# CompSchm.net
KiCad netlist of a schematic drawn in Altium Designer
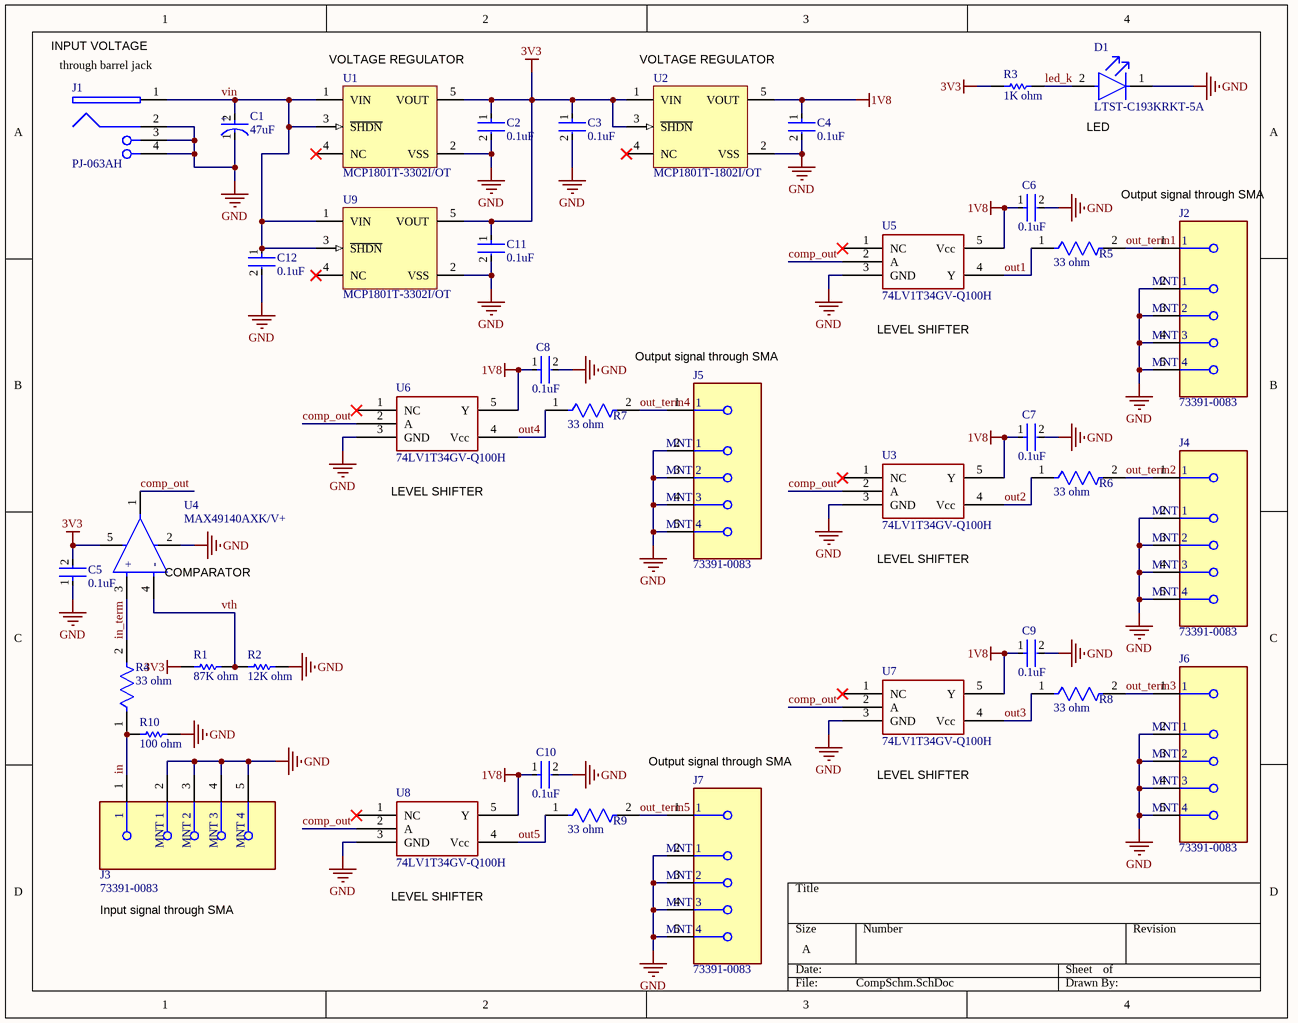
[diagram p0: CompSchm.SchDoc]

(export (version "E")
  (design (tool "Eeschema 10.0.6"))
  (components
    (comp (ref "C1")
      (value "47uF")
      (footprint "FP-T491X476K035AT-MFG")
      (description "CAP TANT 47UF 10% 35V 2917 Part: T491X476K035AT")
      (fields (field (name "TOLERANCE") "10%") (field (name "VOLTAGE") "35V"))
      (libsource (lib "Altium Content Vault") (part "203bc49f2ac43e59fd269a8c329ed05"))
    )
    (comp (ref "C2")
      (value "0.1uF")
      (footprint "FP-CL21-IPC_C")
      (description "CL21 Series 0805 100nF 25V ±10% Tolerance X7R Multilayer Ceramic Chip Capacitor")
      (fields (field (name "VOLTAGE") "25V") (field (name "TOLERANCE") "10%"))
      (libsource (lib "Altium Content Vault") (part "b4654b650e69147ec39a6b967a45e02"))
    )
    (comp (ref "C3")
      (value "0.1uF")
      (footprint "FP-CL21-IPC_C")
      (description "CL21 Series 0805 100nF 25V ±10% Tolerance X7R Multilayer Ceramic Chip Capacitor")
      (fields (field (name "VOLTAGE") "25V") (field (name "TOLERANCE") "10%"))
      (libsource (lib "Altium Content Vault") (part "b4654b650e69147ec39a6b967a45e02"))
    )
    (comp (ref "C4")
      (value "0.1uF")
      (footprint "FP-CL21-IPC_C")
      (description "CL21 Series 0805 100nF 25V ±10% Tolerance X7R Multilayer Ceramic Chip Capacitor")
      (fields (field (name "VOLTAGE") "25V") (field (name "TOLERANCE") "10%"))
      (libsource (lib "Altium Content Vault") (part "b4654b650e69147ec39a6b967a45e02"))
    )
    (comp (ref "C5")
      (value "0.1uF")
      (footprint "FP-CL21-IPC_C")
      (description "CL21 Series 0805 100nF 25V ±10% Tolerance X7R Multilayer Ceramic Chip Capacitor")
      (fields (field (name "VOLTAGE") "25V") (field (name "TOLERANCE") "10%"))
      (libsource (lib "Altium Content Vault") (part "b4654b650e69147ec39a6b967a45e02"))
    )
    (comp (ref "C6")
      (value "0.1uF")
      (footprint "FP-CL21-IPC_C")
      (description "CL21 Series 0805 100nF 25V ±10% Tolerance X7R Multilayer Ceramic Chip Capacitor")
      (fields (field (name "VOLTAGE") "25V") (field (name "TOLERANCE") "10%"))
      (libsource (lib "Altium Content Vault") (part "b4654b650e69147ec39a6b967a45e02"))
    )
    (comp (ref "C7")
      (value "0.1uF")
      (footprint "FP-CL21-IPC_C")
      (description "CL21 Series 0805 100nF 25V ±10% Tolerance X7R Multilayer Ceramic Chip Capacitor")
      (fields (field (name "VOLTAGE") "25V") (field (name "TOLERANCE") "10%"))
      (libsource (lib "Altium Content Vault") (part "b4654b650e69147ec39a6b967a45e02"))
    )
    (comp (ref "C8")
      (value "0.1uF")
      (footprint "FP-CL21-IPC_C")
      (description "CL21 Series 0805 100nF 25V ±10% Tolerance X7R Multilayer Ceramic Chip Capacitor")
      (fields (field (name "VOLTAGE") "25V") (field (name "TOLERANCE") "10%"))
      (libsource (lib "Altium Content Vault") (part "b4654b650e69147ec39a6b967a45e02"))
    )
    (comp (ref "C9")
      (value "0.1uF")
      (footprint "FP-CL21-IPC_C")
      (description "CL21 Series 0805 100nF 25V ±10% Tolerance X7R Multilayer Ceramic Chip Capacitor")
      (fields (field (name "VOLTAGE") "25V") (field (name "TOLERANCE") "10%"))
      (libsource (lib "Altium Content Vault") (part "b4654b650e69147ec39a6b967a45e02"))
    )
    (comp (ref "C10")
      (value "0.1uF")
      (footprint "FP-CL21-IPC_C")
      (description "CL21 Series 0805 100nF 25V ±10% Tolerance X7R Multilayer Ceramic Chip Capacitor")
      (fields (field (name "VOLTAGE") "25V") (field (name "TOLERANCE") "10%"))
      (libsource (lib "Altium Content Vault") (part "b4654b650e69147ec39a6b967a45e02"))
    )
    (comp (ref "C11")
      (value "0.1uF")
      (footprint "FP-CL21-IPC_C")
      (description "CL21 Series 0805 100nF 25V ±10% Tolerance X7R Multilayer Ceramic Chip Capacitor")
      (fields (field (name "VOLTAGE") "25V") (field (name "TOLERANCE") "10%"))
      (libsource (lib "Altium Content Vault") (part "b4654b650e69147ec39a6b967a45e02"))
    )
    (comp (ref "C12")
      (value "0.1uF")
      (footprint "FP-CL21-IPC_C")
      (description "CL21 Series 0805 100nF 25V ±10% Tolerance X7R Multilayer Ceramic Chip Capacitor")
      (fields (field (name "VOLTAGE") "25V") (field (name "TOLERANCE") "10%"))
      (libsource (lib "Altium Content Vault") (part "b4654b650e69147ec39a6b967a45e02"))
    )
    (comp (ref "D1")
      (value "LTST-C193KRKT-5A")
      (footprint "FP-LTST-C193KRKT-5A-MFG")
      (description "LED RED CLEAR CHIP SMD")
      (libsource (lib "Altium Content Vault") (part "8706943c75ba83719d021d2fdc84c58"))
    )
    (comp (ref "J1")
      (value "PJ-063AH")
      (footprint "CUI-PJ-063AH_V")
      (fields (field (name "MANUFACTURER") "CUIInc."))
      (libsource (lib "Altium Content Vault") (part "JACK-2CD2_A"))
    )
    (comp (ref "J2")
      (value "73391-0083")
      (footprint "FP-73391-0083-MFG")
      (description "SMA RA JACK, PCB")
      (libsource (lib "Altium Content Vault") (part "c65b8a639cdaef1819ea20b5466f8fa"))
    )
    (comp (ref "J3")
      (value "73391-0083")
      (footprint "FP-73391-0083-MFG")
      (description "SMA RA JACK, PCB")
      (libsource (lib "") (part "c65b8a639cdaef1819ea20b5466f8fa_1"))
    )
    (comp (ref "J4")
      (value "73391-0083")
      (footprint "FP-73391-0083-MFG")
      (description "SMA RA JACK, PCB")
      (libsource (lib "Altium Content Vault") (part "c65b8a639cdaef1819ea20b5466f8fa"))
    )
    (comp (ref "J5")
      (value "73391-0083")
      (footprint "FP-73391-0083-MFG")
      (description "SMA RA JACK, PCB")
      (libsource (lib "Altium Content Vault") (part "c65b8a639cdaef1819ea20b5466f8fa"))
    )
    (comp (ref "J6")
      (value "73391-0083")
      (footprint "FP-73391-0083-MFG")
      (description "SMA RA JACK, PCB")
      (libsource (lib "Altium Content Vault") (part "c65b8a639cdaef1819ea20b5466f8fa"))
    )
    (comp (ref "J7")
      (value "73391-0083")
      (footprint "FP-73391-0083-MFG")
      (description "SMA RA JACK, PCB")
      (libsource (lib "Altium Content Vault") (part "c65b8a639cdaef1819ea20b5466f8fa"))
    )
    (comp (ref "R1")
      (value "87K ohm")
      (footprint "RESC2013X50X40NL20T20")
      (fields (field (name "PART NUMBER") "RG2012N-123-W-T1") (field (name "MANUFACTURER") "Susumu"))
      (libsource (lib "Altium Content Vault") (part "RES"))
    )
    (comp (ref "R2")
      (value "12K ohm")
      (footprint "RESC2013X50X40NL20T20")
      (fields (field (name "PART NUMBER") "RG2012N-123-W-T1") (field (name "MANUFACTURER") "Susumu"))
      (libsource (lib "Altium Content Vault") (part "RES"))
    )
    (comp (ref "R3")
      (value "1K ohm")
      (footprint "RESC2013X50X40NL20T20")
      (fields (field (name "PART NUMBER") "RG2012N-123-W-T1") (field (name "MANUFACTURER") "Susumu"))
      (libsource (lib "Altium Content Vault") (part "RES"))
    )
    (comp (ref "R4")
      (value "33 ohm")
      (footprint "FP-CRGCQ0805-IPC_C")
      (description "CRGCQ0805 33Ω 0.125W ±200ppm/°C 1% 150V")
      (fields
        (field (name "MANUFACTURER PART NUMBER") "CRGCQ0805F33R")
        (field (name "MANUFACTURER") "TE Connectivity")
      )
      (libsource (lib "Altium Content Vault") (part "1029c3af85768c4190bb7ad29bc67b5"))
    )
    (comp (ref "R5")
      (value "33 ohm")
      (footprint "FP-CRGCQ0805-IPC_C")
      (description "CRGCQ0805 33Ω 0.125W ±200ppm/°C 1% 150V")
      (fields
        (field (name "MANUFACTURER PART NUMBER") "CRGCQ0805F33R")
        (field (name "MANUFACTURER") "TE Connectivity")
      )
      (libsource (lib "Altium Content Vault") (part "1029c3af85768c4190bb7ad29bc67b5"))
    )
    (comp (ref "R6")
      (value "33 ohm")
      (footprint "FP-CRGCQ0805-IPC_C")
      (description "CRGCQ0805 33Ω 0.125W ±200ppm/°C 1% 150V")
      (fields
        (field (name "MANUFACTURER PART NUMBER") "CRGCQ0805F33R")
        (field (name "MANUFACTURER") "TE Connectivity")
      )
      (libsource (lib "Altium Content Vault") (part "1029c3af85768c4190bb7ad29bc67b5"))
    )
    (comp (ref "R7")
      (value "33 ohm")
      (footprint "FP-CRGCQ0805-IPC_C")
      (description "CRGCQ0805 33Ω 0.125W ±200ppm/°C 1% 150V")
      (fields
        (field (name "MANUFACTURER PART NUMBER") "CRGCQ0805F33R")
        (field (name "MANUFACTURER") "TE Connectivity")
      )
      (libsource (lib "Altium Content Vault") (part "1029c3af85768c4190bb7ad29bc67b5"))
    )
    (comp (ref "R8")
      (value "33 ohm")
      (footprint "FP-CRGCQ0805-IPC_C")
      (description "CRGCQ0805 33Ω 0.125W ±200ppm/°C 1% 150V")
      (fields
        (field (name "MANUFACTURER PART NUMBER") "CRGCQ0805F33R")
        (field (name "MANUFACTURER") "TE Connectivity")
      )
      (libsource (lib "Altium Content Vault") (part "1029c3af85768c4190bb7ad29bc67b5"))
    )
    (comp (ref "R9")
      (value "33 ohm")
      (footprint "FP-CRGCQ0805-IPC_C")
      (description "CRGCQ0805 33Ω 0.125W ±200ppm/°C 1% 150V")
      (fields
        (field (name "MANUFACTURER PART NUMBER") "CRGCQ0805F33R")
        (field (name "MANUFACTURER") "TE Connectivity")
      )
      (libsource (lib "Altium Content Vault") (part "1029c3af85768c4190bb7ad29bc67b5"))
    )
    (comp (ref "R10")
      (value "100 ohm")
      (footprint "RESC2013X50X40NL20T20")
      (fields (field (name "PART NUMBER") "RG2012N-123-W-T1") (field (name "MANUFACTURER") "Susumu"))
      (libsource (lib "Altium Content Vault") (part "RES"))
    )
    (comp (ref "U1")
      (value "MCP1801T-3302I/OT")
      (footprint "SOT-23-OT5_M")
      (description "150 mA, High PSRR, Low Quiescent Current LDO, 5-Pin SOT-23, Industrial Temperature, Tape and Reel")
      (libsource (lib "Altium Content Vault") (part "PM-LINEREG-MCP1801-IL5"))
    )
    (comp (ref "U2")
      (value "MCP1801T-1802I/OT")
      (footprint "SOT-23-OT5_M")
      (description "150 mA, High PSRR, Low Quiescent Current LDO, 5-Pin SOT-23, Industrial Temperature, Tape and Reel")
      (libsource (lib "Altium Content Vault") (part "PM-LINEREG-MCP1801-IL5"))
    )
    (comp (ref "U3")
      (value "74LV1T34GV-Q100H")
      (footprint "SOT95P275X110-5N:SOT95P275X110-5N")
      (description "Level Shifter")
      (libsource (lib "74LV1T34GV-Q100H") (part "74LV1T34GV-Q100H"))
    )
    (comp (ref "U4")
      (value "MAX49140AXK/V+")
      (footprint "FP-X5-1C-MFG")
      (description "30NS, LOW-POWER, 3V/5V, RAIL-TO-")
      (libsource (lib "Altium Content Vault") (part "3063e83f23e6bb72aa5a98f7fedc5b1"))
    )
    (comp (ref "U5")
      (value "74LV1T34GV-Q100H")
      (footprint "SOT95P275X110-5N:SOT95P275X110-5N")
      (description "Level Shifter")
      (libsource (lib "74LV1T34GV-Q100H") (part "74LV1T34GV-Q100H"))
    )
    (comp (ref "U6")
      (value "74LV1T34GV-Q100H")
      (footprint "SOT95P275X110-5N:SOT95P275X110-5N")
      (description "Level Shifter")
      (libsource (lib "74LV1T34GV-Q100H") (part "74LV1T34GV-Q100H"))
    )
    (comp (ref "U7")
      (value "74LV1T34GV-Q100H")
      (footprint "SOT95P275X110-5N:SOT95P275X110-5N")
      (description "Level Shifter")
      (libsource (lib "74LV1T34GV-Q100H") (part "74LV1T34GV-Q100H"))
    )
    (comp (ref "U8")
      (value "74LV1T34GV-Q100H")
      (footprint "SOT95P275X110-5N:SOT95P275X110-5N")
      (description "Level Shifter")
      (libsource (lib "74LV1T34GV-Q100H") (part "74LV1T34GV-Q100H"))
    )
    (comp (ref "U9")
      (value "MCP1801T-3302I/OT")
      (footprint "SOT-23-OT5_M")
      (description "150 mA, High PSRR, Low Quiescent Current LDO, 5-Pin SOT-23, Industrial Temperature, Tape and Reel")
      (libsource (lib "Altium Content Vault") (part "PM-LINEREG-MCP1801-IL5"))
    )
  )
  (nets
    (net (code "1") (name "/comp_out") (class "Default")
      (node (ref "U3") (pin "2") (pinfunction "A_2") (pintype "passive"))
      (node (ref "U4") (pin "1") (pinfunction "OUT_1") (pintype "passive"))
      (node (ref "U5") (pin "2") (pinfunction "A_2") (pintype "passive"))
      (node (ref "U6") (pin "2") (pinfunction "A_2") (pintype "passive"))
      (node (ref "U7") (pin "2") (pinfunction "A_2") (pintype "passive"))
      (node (ref "U8") (pin "2") (pinfunction "A_2") (pintype "passive"))
    )
    (net (code "2") (name "/in") (class "Default")
      (node (ref "J3") (pin "1") (pinfunction "1_1") (pintype "passive"))
      (node (ref "R10") (pin "2") (pinfunction "2_2") (pintype "passive"))
      (node (ref "R4") (pin "1") (pinfunction "1_1") (pintype "passive"))
    )
    (net (code "3") (name "/in_term") (class "Default")
      (node (ref "R4") (pin "2") (pinfunction "2_2") (pintype "passive"))
      (node (ref "U4") (pin "3") (pinfunction "IN+_3") (pintype "tri_state"))
    )
    (net (code "4") (name "/led_k") (class "Default")
      (node (ref "D1") (pin "2") (pinfunction "A_2") (pintype "passive"))
      (node (ref "R3") (pin "1") (pinfunction "1_1") (pintype "passive"))
    )
    (net (code "5") (name "/out1") (class "Default")
      (node (ref "R5") (pin "1") (pinfunction "1_1") (pintype "passive"))
      (node (ref "U5") (pin "4") (pinfunction "Vcc_4") (pintype "passive"))
    )
    (net (code "6") (name "/out2") (class "Default")
      (node (ref "R6") (pin "1") (pinfunction "1_1") (pintype "passive"))
      (node (ref "U3") (pin "4") (pinfunction "Vcc_4") (pintype "passive"))
    )
    (net (code "7") (name "/out3") (class "Default")
      (node (ref "R8") (pin "1") (pinfunction "1_1") (pintype "passive"))
      (node (ref "U7") (pin "4") (pinfunction "Vcc_4") (pintype "passive"))
    )
    (net (code "8") (name "/out4") (class "Default")
      (node (ref "R7") (pin "1") (pinfunction "1_1") (pintype "passive"))
      (node (ref "U6") (pin "4") (pinfunction "Vcc_4") (pintype "passive"))
    )
    (net (code "9") (name "/out5") (class "Default")
      (node (ref "R9") (pin "1") (pinfunction "1_1") (pintype "passive"))
      (node (ref "U8") (pin "4") (pinfunction "Vcc_4") (pintype "passive"))
    )
    (net (code "10") (name "/out_term1") (class "Default")
      (node (ref "J2") (pin "1") (pinfunction "1_1") (pintype "passive"))
      (node (ref "R5") (pin "2") (pinfunction "2_2") (pintype "passive"))
    )
    (net (code "11") (name "/out_term2") (class "Default")
      (node (ref "J4") (pin "1") (pinfunction "1_1") (pintype "passive"))
      (node (ref "R6") (pin "2") (pinfunction "2_2") (pintype "passive"))
    )
    (net (code "12") (name "/out_term3") (class "Default")
      (node (ref "J6") (pin "1") (pinfunction "1_1") (pintype "passive"))
      (node (ref "R8") (pin "2") (pinfunction "2_2") (pintype "passive"))
    )
    (net (code "13") (name "/out_term4") (class "Default")
      (node (ref "J5") (pin "1") (pinfunction "1_1") (pintype "passive"))
      (node (ref "R7") (pin "2") (pinfunction "2_2") (pintype "passive"))
    )
    (net (code "14") (name "/out_term5") (class "Default")
      (node (ref "J7") (pin "1") (pinfunction "1_1") (pintype "passive"))
      (node (ref "R9") (pin "2") (pinfunction "2_2") (pintype "passive"))
    )
    (net (code "15") (name "/vin") (class "Default")
      (node (ref "C1") (pin "2") (pinfunction "A_2") (pintype "passive"))
      (node (ref "C12") (pin "1") (pinfunction "1_1") (pintype "passive"))
      (node (ref "J1") (pin "1") (pinfunction "1_1") (pintype "passive"))
      (node (ref "U1") (pin "1") (pinfunction "VIN_1") (pintype "power_in"))
      (node (ref "U1") (pin "3") (pinfunction "~{SHDN}_3") (pintype "input"))
      (node (ref "U9") (pin "1") (pinfunction "VIN_1") (pintype "power_in"))
      (node (ref "U9") (pin "3") (pinfunction "~{SHDN}_3") (pintype "input"))
    )
    (net (code "16") (name "/vth") (class "Default")
      (node (ref "R1") (pin "1") (pinfunction "1_1") (pintype "passive"))
      (node (ref "R2") (pin "2") (pinfunction "2_2") (pintype "passive"))
      (node (ref "U4") (pin "4") (pinfunction "IN-_4") (pintype "tri_state"))
    )
    (net (code "17") (name "1V8") (class "Default")
      (node (ref "C10") (pin "1") (pinfunction "1_1") (pintype "passive"))
      (node (ref "C4") (pin "1") (pinfunction "1_1") (pintype "passive"))
      (node (ref "C6") (pin "1") (pinfunction "1_1") (pintype "passive"))
      (node (ref "C7") (pin "1") (pinfunction "1_1") (pintype "passive"))
      (node (ref "C8") (pin "1") (pinfunction "1_1") (pintype "passive"))
      (node (ref "C9") (pin "1") (pinfunction "1_1") (pintype "passive"))
      (node (ref "U2") (pin "5") (pinfunction "VOUT_5") (pintype "power_in"))
      (node (ref "U3") (pin "5") (pinfunction "Y_5") (pintype "passive"))
      (node (ref "U5") (pin "5") (pinfunction "Y_5") (pintype "passive"))
      (node (ref "U6") (pin "5") (pinfunction "Y_5") (pintype "passive"))
      (node (ref "U7") (pin "5") (pinfunction "Y_5") (pintype "passive"))
      (node (ref "U8") (pin "5") (pinfunction "Y_5") (pintype "passive"))
    )
    (net (code "18") (name "3V3") (class "Default")
      (node (ref "C11") (pin "1") (pinfunction "1_1") (pintype "passive"))
      (node (ref "C2") (pin "1") (pinfunction "1_1") (pintype "passive"))
      (node (ref "C3") (pin "1") (pinfunction "1_1") (pintype "passive"))
      (node (ref "C5") (pin "2") (pinfunction "2_2") (pintype "passive"))
      (node (ref "R1") (pin "2") (pinfunction "2_2") (pintype "passive"))
      (node (ref "R3") (pin "2") (pinfunction "2_2") (pintype "passive"))
      (node (ref "U1") (pin "5") (pinfunction "VOUT_5") (pintype "power_in"))
      (node (ref "U2") (pin "1") (pinfunction "VIN_1") (pintype "power_in"))
      (node (ref "U2") (pin "3") (pinfunction "~{SHDN}_3") (pintype "input"))
      (node (ref "U4") (pin "5") (pinfunction "VDD_5") (pintype "power_in"))
      (node (ref "U9") (pin "5") (pinfunction "VOUT_5") (pintype "power_in"))
    )
    (net (code "19") (name "GND") (class "Default")
      (node (ref "C1") (pin "1") (pinfunction "C_1") (pintype "passive"))
      (node (ref "C10") (pin "2") (pinfunction "2_2") (pintype "passive"))
      (node (ref "C11") (pin "2") (pinfunction "2_2") (pintype "passive"))
      (node (ref "C12") (pin "2") (pinfunction "2_2") (pintype "passive"))
      (node (ref "C2") (pin "2") (pinfunction "2_2") (pintype "passive"))
      (node (ref "C3") (pin "2") (pinfunction "2_2") (pintype "passive"))
      (node (ref "C4") (pin "2") (pinfunction "2_2") (pintype "passive"))
      (node (ref "C5") (pin "1") (pinfunction "1_1") (pintype "passive"))
      (node (ref "C6") (pin "2") (pinfunction "2_2") (pintype "passive"))
      (node (ref "C7") (pin "2") (pinfunction "2_2") (pintype "passive"))
      (node (ref "C8") (pin "2") (pinfunction "2_2") (pintype "passive"))
      (node (ref "C9") (pin "2") (pinfunction "2_2") (pintype "passive"))
      (node (ref "D1") (pin "1") (pinfunction "C_1") (pintype "passive"))
      (node (ref "J1") (pin "2") (pinfunction "2_2") (pintype "passive"))
      (node (ref "J1") (pin "3") (pinfunction "SHLD_3") (pintype "passive"))
      (node (ref "J1") (pin "4") (pinfunction "SHLD_4") (pintype "passive"))
      (node (ref "J2") (pin "2") (pinfunction "MNT_1_2") (pintype "passive"))
      (node (ref "J2") (pin "3") (pinfunction "MNT_2_3") (pintype "passive"))
      (node (ref "J2") (pin "4") (pinfunction "MNT_3_4") (pintype "passive"))
      (node (ref "J2") (pin "5") (pinfunction "MNT_4_5") (pintype "passive"))
      (node (ref "J3") (pin "2") (pinfunction "MNT_1_2") (pintype "passive"))
      (node (ref "J3") (pin "3") (pinfunction "MNT_2_3") (pintype "passive"))
      (node (ref "J3") (pin "4") (pinfunction "MNT_3_4") (pintype "passive"))
      (node (ref "J3") (pin "5") (pinfunction "MNT_4_5") (pintype "passive"))
      (node (ref "J4") (pin "2") (pinfunction "MNT_1_2") (pintype "passive"))
      (node (ref "J4") (pin "3") (pinfunction "MNT_2_3") (pintype "passive"))
      (node (ref "J4") (pin "4") (pinfunction "MNT_3_4") (pintype "passive"))
      (node (ref "J4") (pin "5") (pinfunction "MNT_4_5") (pintype "passive"))
      (node (ref "J5") (pin "2") (pinfunction "MNT_1_2") (pintype "passive"))
      (node (ref "J5") (pin "3") (pinfunction "MNT_2_3") (pintype "passive"))
      (node (ref "J5") (pin "4") (pinfunction "MNT_3_4") (pintype "passive"))
      (node (ref "J5") (pin "5") (pinfunction "MNT_4_5") (pintype "passive"))
      (node (ref "J6") (pin "2") (pinfunction "MNT_1_2") (pintype "passive"))
      (node (ref "J6") (pin "3") (pinfunction "MNT_2_3") (pintype "passive"))
      (node (ref "J6") (pin "4") (pinfunction "MNT_3_4") (pintype "passive"))
      (node (ref "J6") (pin "5") (pinfunction "MNT_4_5") (pintype "passive"))
      (node (ref "J7") (pin "2") (pinfunction "MNT_1_2") (pintype "passive"))
      (node (ref "J7") (pin "3") (pinfunction "MNT_2_3") (pintype "passive"))
      (node (ref "J7") (pin "4") (pinfunction "MNT_3_4") (pintype "passive"))
      (node (ref "J7") (pin "5") (pinfunction "MNT_4_5") (pintype "passive"))
      (node (ref "R10") (pin "1") (pinfunction "1_1") (pintype "passive"))
      (node (ref "R2") (pin "1") (pinfunction "1_1") (pintype "passive"))
      (node (ref "U1") (pin "2") (pinfunction "VSS_2") (pintype "power_in"))
      (node (ref "U2") (pin "2") (pinfunction "VSS_2") (pintype "power_in"))
      (node (ref "U3") (pin "3") (pinfunction "GND_3") (pintype "passive"))
      (node (ref "U4") (pin "2") (pinfunction "GND_2") (pintype "power_in"))
      (node (ref "U5") (pin "3") (pinfunction "GND_3") (pintype "passive"))
      (node (ref "U6") (pin "3") (pinfunction "GND_3") (pintype "passive"))
      (node (ref "U7") (pin "3") (pinfunction "GND_3") (pintype "passive"))
      (node (ref "U8") (pin "3") (pinfunction "GND_3") (pintype "passive"))
      (node (ref "U9") (pin "2") (pinfunction "VSS_2") (pintype "power_in"))
    )
    (net (code "20") (name "unconnected-(U1-NC-Pad4)") (class "Default")
      (node (ref "U1") (pin "4") (pinfunction "NC_4") (pintype "passive+no_connect"))
    )
    (net (code "21") (name "unconnected-(U2-NC-Pad4)") (class "Default")
      (node (ref "U2") (pin "4") (pinfunction "NC_4") (pintype "passive+no_connect"))
    )
    (net (code "22") (name "unconnected-(U3-NC-Pad1)") (class "Default")
      (node (ref "U3") (pin "1") (pinfunction "NC_1") (pintype "passive+no_connect"))
    )
    (net (code "23") (name "unconnected-(U5-NC-Pad1)") (class "Default")
      (node (ref "U5") (pin "1") (pinfunction "NC_1") (pintype "passive+no_connect"))
    )
    (net (code "24") (name "unconnected-(U6-NC-Pad1)") (class "Default")
      (node (ref "U6") (pin "1") (pinfunction "NC_1") (pintype "passive+no_connect"))
    )
    (net (code "25") (name "unconnected-(U7-NC-Pad1)") (class "Default")
      (node (ref "U7") (pin "1") (pinfunction "NC_1") (pintype "passive+no_connect"))
    )
    (net (code "26") (name "unconnected-(U8-NC-Pad1)") (class "Default")
      (node (ref "U8") (pin "1") (pinfunction "NC_1") (pintype "passive+no_connect"))
    )
    (net (code "27") (name "unconnected-(U9-NC-Pad4)") (class "Default")
      (node (ref "U9") (pin "4") (pinfunction "NC_4") (pintype "passive+no_connect"))
    )
  )
)
